# SCH.net
KiCad netlist of a schematic drawn in Altium Designer
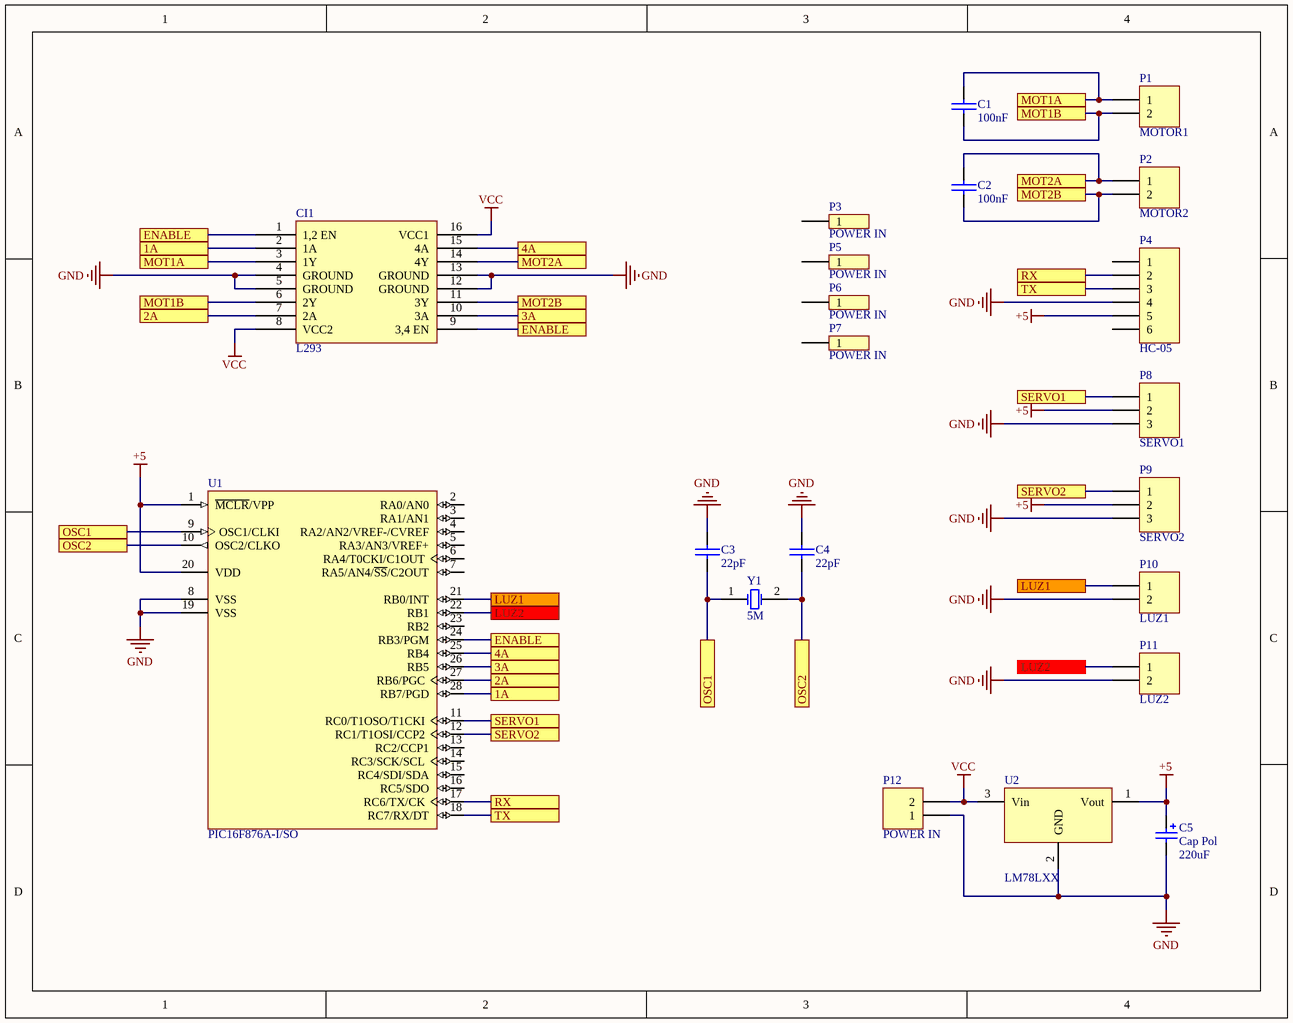
[diagram p0: SCH.schdoc]

(export (version "E")
  (design (tool "Eeschema 10.0.6"))
  (components
    (comp (ref "C1")
      (value "100nF")
      (footprint "CAP0.15")
      (libsource (lib "LIBRERIA DIAZ BAEZ") (part "CAP"))
    )
    (comp (ref "C2")
      (value "100nF")
      (footprint "CAP0.15")
      (libsource (lib "LIBRERIA DIAZ BAEZ") (part "CAP"))
    )
    (comp (ref "C3") (value "22pF") (footprint "CAP0.15") (libsource (lib "LIBRERIA DIAZ BAEZ") (part "CAP")))
    (comp (ref "C4") (value "22pF") (footprint "CAP0.15") (libsource (lib "LIBRERIA DIAZ BAEZ") (part "CAP")))
    (comp (ref "C5")
      (value "Cap Pol")
      (footprint "ELECTROLITICO 5X10")
      (description "Polarized Capacitor (Surface Mount)")
      (fields (field (name "ALTIUM_VALUE") "220uF") (field (name "PUBLISHER") "Altium Limited"))
      (libsource (lib "LIBRERIA DIAZ BAEZ") (part "Cap Pol"))
    )
    (comp (ref "CI1")
      (value "L293")
      (footprint "DIP16")
      (description "Driver_Motor")
      (fields (field (name "PUBLISHER") "Altium Limited"))
      (libsource (lib "LIBRERIA DIAZ BAEZ") (part "L293"))
    )
    (comp (ref "P1")
      (value "MOTOR1")
      (footprint "BORNERA2 azul")
      (description "Header, 2-Pin")
      (fields (field (name "PUBLISHER") "Altium Limited"))
      (libsource (lib "LIBRERIA DIAZ BAEZ") (part "Header 2"))
    )
    (comp (ref "P2")
      (value "MOTOR2")
      (footprint "BORNERA2 azul")
      (description "Header, 2-Pin")
      (fields (field (name "PUBLISHER") "Altium Limited"))
      (libsource (lib "LIBRERIA DIAZ BAEZ") (part "Header 2"))
    )
    (comp (ref "P3")
      (value "POWER IN")
      (footprint "TORNILLO")
      (description "Header, 2-Pin")
      (fields (field (name "PUBLISHER") "Altium Limited"))
      (libsource (lib "LIBRERIA DIAZ BAEZ") (part "Header 1"))
    )
    (comp (ref "P4")
      (value "HC-05")
      (footprint "Header 1X6")
      (description "Header, 6-Pin")
      (fields (field (name "PUBLISHER") "Altium Limited"))
      (libsource (lib "LIBRERIA DIAZ BAEZ") (part "Header 6"))
    )
    (comp (ref "P5")
      (value "POWER IN")
      (footprint "TORNILLO")
      (description "Header, 2-Pin")
      (fields (field (name "PUBLISHER") "Altium Limited"))
      (libsource (lib "LIBRERIA DIAZ BAEZ") (part "Header 1"))
    )
    (comp (ref "P6")
      (value "POWER IN")
      (footprint "TORNILLO")
      (description "Header, 2-Pin")
      (fields (field (name "PUBLISHER") "Altium Limited"))
      (libsource (lib "LIBRERIA DIAZ BAEZ") (part "Header 1"))
    )
    (comp (ref "P7")
      (value "POWER IN")
      (footprint "TORNILLO")
      (description "Header, 2-Pin")
      (fields (field (name "PUBLISHER") "Altium Limited"))
      (libsource (lib "LIBRERIA DIAZ BAEZ") (part "Header 1"))
    )
    (comp (ref "P8")
      (value "SERVO1")
      (footprint "Header 1X3")
      (description "Header, 3-Pin")
      (fields (field (name "PUBLISHER") "Altium Limited"))
      (libsource (lib "LIBRERIA DIAZ BAEZ") (part "Header 3"))
    )
    (comp (ref "P9")
      (value "SERVO2")
      (footprint "Header 1X3")
      (description "Header, 3-Pin")
      (fields (field (name "PUBLISHER") "Altium Limited"))
      (libsource (lib "LIBRERIA DIAZ BAEZ") (part "Header 3"))
    )
    (comp (ref "P10")
      (value "LUZ1")
      (footprint "HEADER1X2")
      (description "Header, 2-Pin")
      (fields (field (name "PUBLISHER") "Altium Limited"))
      (libsource (lib "LIBRERIA DIAZ BAEZ") (part "Header 2"))
    )
    (comp (ref "P11")
      (value "LUZ2")
      (footprint "HEADER1X2")
      (description "Header, 2-Pin")
      (fields (field (name "PUBLISHER") "Altium Limited"))
      (libsource (lib "LIBRERIA DIAZ BAEZ") (part "Header 2"))
    )
    (comp (ref "P12")
      (value "POWER IN")
      (footprint "BORNERA2 azul")
      (description "Header, 2-Pin")
      (fields (field (name "PUBLISHER") "Altium Limited"))
      (libsource (lib "") (part "Header 2_1"))
    )
    (comp (ref "U1")
      (value "PIC16F876A-I/SO")
      (footprint "DIP28")
      (fields (field (name "PUBLISHER") "Altium Limited"))
      (libsource (lib "Microchip Microcontroller 8-Bit PIC16") (part "PIC16F876A-I/SO"))
    )
    (comp (ref "U2")
      (value "LM78LXX")
      (footprint "TO220")
      (libsource (lib "LIBRERIA DIAZ BAEZ") (part "LM78LXX"))
    )
    (comp (ref "Y1")
      (value "5M")
      (footprint "HP49-S")
      (description "Crystal Oscillator")
      (fields (field (name "PUBLISHER") "Altium Limited"))
      (libsource (lib "LIBRERIA DIAZ BAEZ") (part "XTAL"))
    )
  )
  (nets
    (net (code "1") (name "+5") (class "Default")
      (node (ref "C5") (pin "1") (pinfunction "1_1") (pintype "passive"))
      (node (ref "P4") (pin "5") (pinfunction "5_5") (pintype "passive"))
      (node (ref "P8") (pin "2") (pinfunction "2_2") (pintype "passive"))
      (node (ref "P9") (pin "2") (pinfunction "2_2") (pintype "passive"))
      (node (ref "U1") (pin "1") (pinfunction "~{MCLR}/VPP_1") (pintype "input"))
      (node (ref "U1") (pin "20") (pinfunction "VDD_20") (pintype "power_in"))
      (node (ref "U2") (pin "1") (pinfunction "Vout_1") (pintype "passive"))
    )
    (net (code "2") (name "/1A") (class "Default")
      (node (ref "CI1") (pin "2") (pinfunction "1A_2") (pintype "passive"))
      (node (ref "U1") (pin "28") (pinfunction "RB7/PGD_28") (pintype "bidirectional"))
    )
    (net (code "3") (name "/2A") (class "Default")
      (node (ref "CI1") (pin "7") (pinfunction "2A_7") (pintype "passive"))
      (node (ref "U1") (pin "27") (pinfunction "RB6/PGC_27") (pintype "bidirectional"))
    )
    (net (code "4") (name "/3A") (class "Default")
      (node (ref "CI1") (pin "10") (pinfunction "3A_10") (pintype "passive"))
      (node (ref "U1") (pin "26") (pinfunction "RB5_26") (pintype "bidirectional"))
    )
    (net (code "5") (name "/4A") (class "Default")
      (node (ref "CI1") (pin "15") (pinfunction "4A_15") (pintype "passive"))
      (node (ref "U1") (pin "25") (pinfunction "RB4_25") (pintype "bidirectional"))
    )
    (net (code "6") (name "/ENABLE") (class "Default")
      (node (ref "CI1") (pin "1") (pinfunction "1,2_EN_1") (pintype "passive"))
      (node (ref "CI1") (pin "9") (pinfunction "3,4_EN_9") (pintype "passive"))
      (node (ref "U1") (pin "24") (pinfunction "RB3/PGM_24") (pintype "bidirectional"))
    )
    (net (code "7") (name "/LUZ1") (class "Default")
      (node (ref "P10") (pin "1") (pinfunction "1_1") (pintype "passive"))
      (node (ref "U1") (pin "21") (pinfunction "RB0/INT_21") (pintype "bidirectional"))
    )
    (net (code "8") (name "/LUZ2") (class "Default")
      (node (ref "P11") (pin "1") (pinfunction "1_1") (pintype "passive"))
      (node (ref "U1") (pin "22") (pinfunction "RB1_22") (pintype "bidirectional"))
    )
    (net (code "9") (name "/MOT1A") (class "Default")
      (node (ref "C1") (pin "1") (pinfunction "1_1") (pintype "passive"))
      (node (ref "CI1") (pin "3") (pinfunction "1Y_3") (pintype "passive"))
      (node (ref "P1") (pin "1") (pinfunction "1_1") (pintype "passive"))
    )
    (net (code "10") (name "/MOT1B") (class "Default")
      (node (ref "C1") (pin "2") (pinfunction "2_2") (pintype "passive"))
      (node (ref "CI1") (pin "6") (pinfunction "2Y_6") (pintype "passive"))
      (node (ref "P1") (pin "2") (pinfunction "2_2") (pintype "passive"))
    )
    (net (code "11") (name "/MOT2A") (class "Default")
      (node (ref "C2") (pin "1") (pinfunction "1_1") (pintype "passive"))
      (node (ref "CI1") (pin "14") (pinfunction "4Y_14") (pintype "passive"))
      (node (ref "P2") (pin "1") (pinfunction "1_1") (pintype "passive"))
    )
    (net (code "12") (name "/MOT2B") (class "Default")
      (node (ref "C2") (pin "2") (pinfunction "2_2") (pintype "passive"))
      (node (ref "CI1") (pin "11") (pinfunction "3Y_11") (pintype "passive"))
      (node (ref "P2") (pin "2") (pinfunction "2_2") (pintype "passive"))
    )
    (net (code "13") (name "/OSC1") (class "Default")
      (node (ref "C3") (pin "2") (pinfunction "2_2") (pintype "passive"))
      (node (ref "U1") (pin "9") (pinfunction "OSC1/CLKI_9") (pintype "input"))
      (node (ref "Y1") (pin "1") (pinfunction "OSC1_1") (pintype "passive"))
    )
    (net (code "14") (name "/OSC2") (class "Default")
      (node (ref "C4") (pin "2") (pinfunction "2_2") (pintype "passive"))
      (node (ref "U1") (pin "10") (pinfunction "OSC2/CLKO_10") (pintype "output"))
      (node (ref "Y1") (pin "2") (pinfunction "OSC2_2") (pintype "passive"))
    )
    (net (code "15") (name "/RX") (class "Default")
      (node (ref "P4") (pin "2") (pinfunction "2_2") (pintype "passive"))
      (node (ref "U1") (pin "17") (pinfunction "RC6/TX/CK_17") (pintype "bidirectional"))
    )
    (net (code "16") (name "/SERVO1") (class "Default")
      (node (ref "P8") (pin "1") (pinfunction "1_1") (pintype "passive"))
      (node (ref "U1") (pin "11") (pinfunction "RC0/T1OSO/T1CKI_11") (pintype "bidirectional"))
    )
    (net (code "17") (name "/SERVO2") (class "Default")
      (node (ref "P9") (pin "1") (pinfunction "1_1") (pintype "passive"))
      (node (ref "U1") (pin "12") (pinfunction "RC1/T1OSI/CCP2_12") (pintype "bidirectional"))
    )
    (net (code "18") (name "/TX") (class "Default")
      (node (ref "P4") (pin "3") (pinfunction "3_3") (pintype "passive"))
      (node (ref "U1") (pin "18") (pinfunction "RC7/RX/DT_18") (pintype "bidirectional"))
    )
    (net (code "19") (name "GND") (class "Default")
      (node (ref "C3") (pin "1") (pinfunction "1_1") (pintype "passive"))
      (node (ref "C4") (pin "1") (pinfunction "1_1") (pintype "passive"))
      (node (ref "C5") (pin "2") (pinfunction "2_2") (pintype "passive"))
      (node (ref "CI1") (pin "12") (pinfunction "GROUND_12") (pintype "passive"))
      (node (ref "CI1") (pin "13") (pinfunction "GROUND_13") (pintype "passive"))
      (node (ref "CI1") (pin "4") (pinfunction "GROUND_4") (pintype "passive"))
      (node (ref "CI1") (pin "5") (pinfunction "GROUND_5") (pintype "passive"))
      (node (ref "P10") (pin "2") (pinfunction "2_2") (pintype "passive"))
      (node (ref "P11") (pin "2") (pinfunction "2_2") (pintype "passive"))
      (node (ref "P12") (pin "1") (pinfunction "1_1") (pintype "passive"))
      (node (ref "P4") (pin "4") (pinfunction "4_4") (pintype "passive"))
      (node (ref "P8") (pin "3") (pinfunction "3_3") (pintype "passive"))
      (node (ref "P9") (pin "3") (pinfunction "3_3") (pintype "passive"))
      (node (ref "U1") (pin "19") (pinfunction "VSS_19") (pintype "power_in"))
      (node (ref "U1") (pin "8") (pinfunction "VSS_8") (pintype "power_in"))
      (node (ref "U2") (pin "2") (pinfunction "GND_2") (pintype "passive"))
    )
    (net (code "20") (name "VCC") (class "Default")
      (node (ref "CI1") (pin "16") (pinfunction "VCC1_16") (pintype "passive"))
      (node (ref "CI1") (pin "8") (pinfunction "VCC2_8") (pintype "passive"))
      (node (ref "P12") (pin "2") (pinfunction "2_2") (pintype "passive"))
      (node (ref "U2") (pin "3") (pinfunction "Vin_3") (pintype "passive"))
    )
    (net (code "21") (name "unconnected-(P3-Pad1)") (class "Default")
      (node (ref "P3") (pin "1") (pinfunction "1_1") (pintype "passive"))
    )
    (net (code "22") (name "unconnected-(P4-Pad1)") (class "Default")
      (node (ref "P4") (pin "1") (pinfunction "1_1") (pintype "passive"))
    )
    (net (code "23") (name "unconnected-(P4-Pad6)") (class "Default")
      (node (ref "P4") (pin "6") (pinfunction "6_6") (pintype "passive"))
    )
    (net (code "24") (name "unconnected-(P5-Pad1)") (class "Default")
      (node (ref "P5") (pin "1") (pinfunction "1_1") (pintype "passive"))
    )
    (net (code "25") (name "unconnected-(P6-Pad1)") (class "Default")
      (node (ref "P6") (pin "1") (pinfunction "1_1") (pintype "passive"))
    )
    (net (code "26") (name "unconnected-(P7-Pad1)") (class "Default")
      (node (ref "P7") (pin "1") (pinfunction "1_1") (pintype "passive"))
    )
    (net (code "27") (name "unconnected-(U1-RA0{slash}AN0-Pad2)") (class "Default")
      (node (ref "U1") (pin "2") (pinfunction "RA0/AN0_2") (pintype "bidirectional"))
    )
    (net (code "28") (name "unconnected-(U1-RA1{slash}AN1-Pad3)") (class "Default")
      (node (ref "U1") (pin "3") (pinfunction "RA1/AN1_3") (pintype "bidirectional"))
    )
    (net (code "29") (name "unconnected-(U1-RA2{slash}AN2{slash}VREF-{slash}CVREF-Pad4)") (class "Default")
      (node (ref "U1") (pin "4") (pinfunction "RA2/AN2/VREF-/CVREF_4") (pintype "bidirectional"))
    )
    (net (code "30") (name "unconnected-(U1-RA3{slash}AN3{slash}VREF+-Pad5)") (class "Default")
      (node (ref "U1") (pin "5") (pinfunction "RA3/AN3/VREF+_5") (pintype "bidirectional"))
    )
    (net (code "31") (name "unconnected-(U1-RA4{slash}T0CKI{slash}C1OUT-Pad6)") (class "Default")
      (node (ref "U1") (pin "6") (pinfunction "RA4/T0CKI/C1OUT_6") (pintype "bidirectional"))
    )
    (net (code "32") (name "unconnected-(U1-RA5{slash}AN4{slash}~{SS}{slash}C2OUT-Pad7)") (class "Default")
      (node (ref "U1") (pin "7") (pinfunction "RA5/AN4/~{SS}/C2OUT_7") (pintype "bidirectional"))
    )
    (net (code "33") (name "unconnected-(U1-RB2-Pad23)") (class "Default")
      (node (ref "U1") (pin "23") (pinfunction "RB2_23") (pintype "bidirectional"))
    )
    (net (code "34") (name "unconnected-(U1-RC2{slash}CCP1-Pad13)") (class "Default")
      (node (ref "U1") (pin "13") (pinfunction "RC2/CCP1_13") (pintype "bidirectional"))
    )
    (net (code "35") (name "unconnected-(U1-RC3{slash}SCK{slash}SCL-Pad14)") (class "Default")
      (node (ref "U1") (pin "14") (pinfunction "RC3/SCK/SCL_14") (pintype "bidirectional"))
    )
    (net (code "36") (name "unconnected-(U1-RC4{slash}SDI{slash}SDA-Pad15)") (class "Default")
      (node (ref "U1") (pin "15") (pinfunction "RC4/SDI/SDA_15") (pintype "bidirectional"))
    )
    (net (code "37") (name "unconnected-(U1-RC5{slash}SDO-Pad16)") (class "Default")
      (node (ref "U1") (pin "16") (pinfunction "RC5/SDO_16") (pintype "bidirectional"))
    )
  )
)
